# ADC_SMA_WBC1-1.net
KiCad netlist of a schematic drawn in Altium Designer
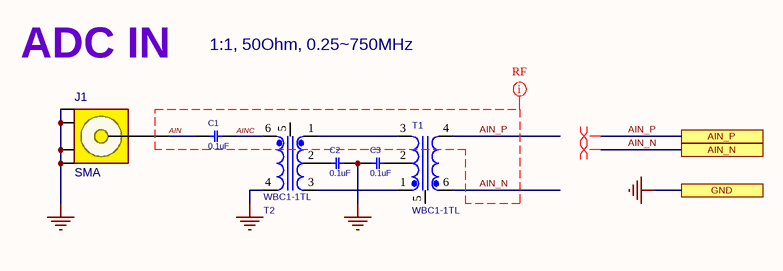
[diagram p0: ADC_SMA_WBC1-1.SchDoc]

(export (version "E")
  (design (tool "Eeschema 10.0.6"))
  (components
    (comp (ref "C1")
      (value "0.1uF")
      (footprint "C0402")
      (description "CAP, MLCC")
      (fields (field (name "MANF_P#") "GRM155R61E104") (field (name "MANF") "Murata"))
      (libsource (lib "mlcc_smd_passive") (part "CAP_SMD_MLCC_100n50T"))
    )
    (comp (ref "C2")
      (value "0.1uF")
      (footprint "C0402")
      (description "CAP, MLCC")
      (fields (field (name "MANF_P#") "GRM155R61E104") (field (name "MANF") "Murata"))
      (libsource (lib "mlcc_smd_passive") (part "CAP_SMD_MLCC_100n50T"))
    )
    (comp (ref "C3")
      (value "0.1uF")
      (footprint "C0402")
      (description "CAP, MLCC")
      (fields (field (name "MANF_P#") "GRM155R61E104") (field (name "MANF") "Murata"))
      (libsource (lib "mlcc_smd_passive") (part "CAP_SMD_MLCC_100n50T"))
    )
    (comp (ref "J1")
      (value "SMA")
      (footprint "SMA_ST")
      (description "CONN, RF, SMA, STRAIGHT")
      (fields (field (name "MANF_P#") "142-0701-201") (field (name "MANF") "Johnson"))
      (libsource (lib "conn_rf") (part "CONN_RF_SMA_ST"))
    )
    (comp (ref "T1")
      (value "WBC1-1TL")
      (footprint "TRNS150_6_450X420")
      (description "RF Transformer, 1:1, 50Ohm, 0.25~750MHz")
      (fields (field (name "MANF") "Coilcraft"))
      (libsource (lib "transformer_rf") (part "WBC1-1TL"))
    )
    (comp (ref "T2")
      (value "WBC1-1TL")
      (footprint "TRNS150_6_450X420")
      (description "RF Transformer, 1:1, 50Ohm, 0.25~750MHz")
      (fields (field (name "MANF") "Coilcraft"))
      (libsource (lib "transformer_rf") (part "WBC1-1TL"))
    )
  )
  (nets
    (net (code "1") (name "/AIN") (class "Default")
      (node (ref "C1") (pin "1") (pinfunction "1_1") (pintype "passive"))
      (node (ref "J1") (pin "1") (pinfunction "SIG_1") (pintype "passive"))
    )
    (net (code "2") (name "/AINC") (class "Default")
      (node (ref "C1") (pin "2") (pinfunction "2_2") (pintype "passive"))
      (node (ref "T2") (pin "6") (pinfunction "SECDOT_6") (pintype "passive"))
    )
    (net (code "3") (name "/AIN_N") (class "Default")
      (node (ref "T1") (pin "6") (pinfunction "SECDOT_6") (pintype "passive"))
    )
    (net (code "4") (name "/AIN_P") (class "Default")
      (node (ref "T1") (pin "4") (pinfunction "SEC_4") (pintype "passive"))
    )
    (net (code "5") (name "GND") (class "Default")
      (node (ref "C2") (pin "2") (pinfunction "2_2") (pintype "passive"))
      (node (ref "C3") (pin "1") (pinfunction "1_1") (pintype "passive"))
      (node (ref "J1") (pin "2") (pinfunction "G1_2") (pintype "passive"))
      (node (ref "J1") (pin "3") (pinfunction "G2_3") (pintype "passive"))
      (node (ref "J1") (pin "4") (pinfunction "G3_4") (pintype "passive"))
      (node (ref "J1") (pin "5") (pinfunction "G4_5") (pintype "passive"))
      (node (ref "T2") (pin "4") (pinfunction "SEC_4") (pintype "passive"))
    )
    (net (code "6") (name "Net-(T1-PRI)") (class "Default")
      (node (ref "T1") (pin "3") (pinfunction "PRI_3") (pintype "passive"))
      (node (ref "T2") (pin "1") (pinfunction "PRIDOT_1") (pintype "passive"))
    )
    (net (code "7") (name "Net-(T1-PRICT)") (class "Default")
      (node (ref "C3") (pin "2") (pinfunction "2_2") (pintype "passive"))
      (node (ref "T1") (pin "2") (pinfunction "PRICT_2") (pintype "passive"))
    )
    (net (code "8") (name "Net-(T1-PRIDOT)") (class "Default")
      (node (ref "T1") (pin "1") (pinfunction "PRIDOT_1") (pintype "passive"))
      (node (ref "T2") (pin "3") (pinfunction "PRI_3") (pintype "passive"))
    )
    (net (code "9") (name "Net-(T2-PRICT)") (class "Default")
      (node (ref "C2") (pin "1") (pinfunction "1_1") (pintype "passive"))
      (node (ref "T2") (pin "2") (pinfunction "PRICT_2") (pintype "passive"))
    )
    (net (code "10") (name "unconnected-(T1-NC-Pad5)") (class "Default")
      (node (ref "T1") (pin "5") (pinfunction "NC_5") (pintype "passive"))
    )
    (net (code "11") (name "unconnected-(T2-NC-Pad5)") (class "Default")
      (node (ref "T2") (pin "5") (pinfunction "NC_5") (pintype "passive"))
    )
  )
)
